# POW_CONT.net
KiCad netlist of a schematic drawn in Altium Designer
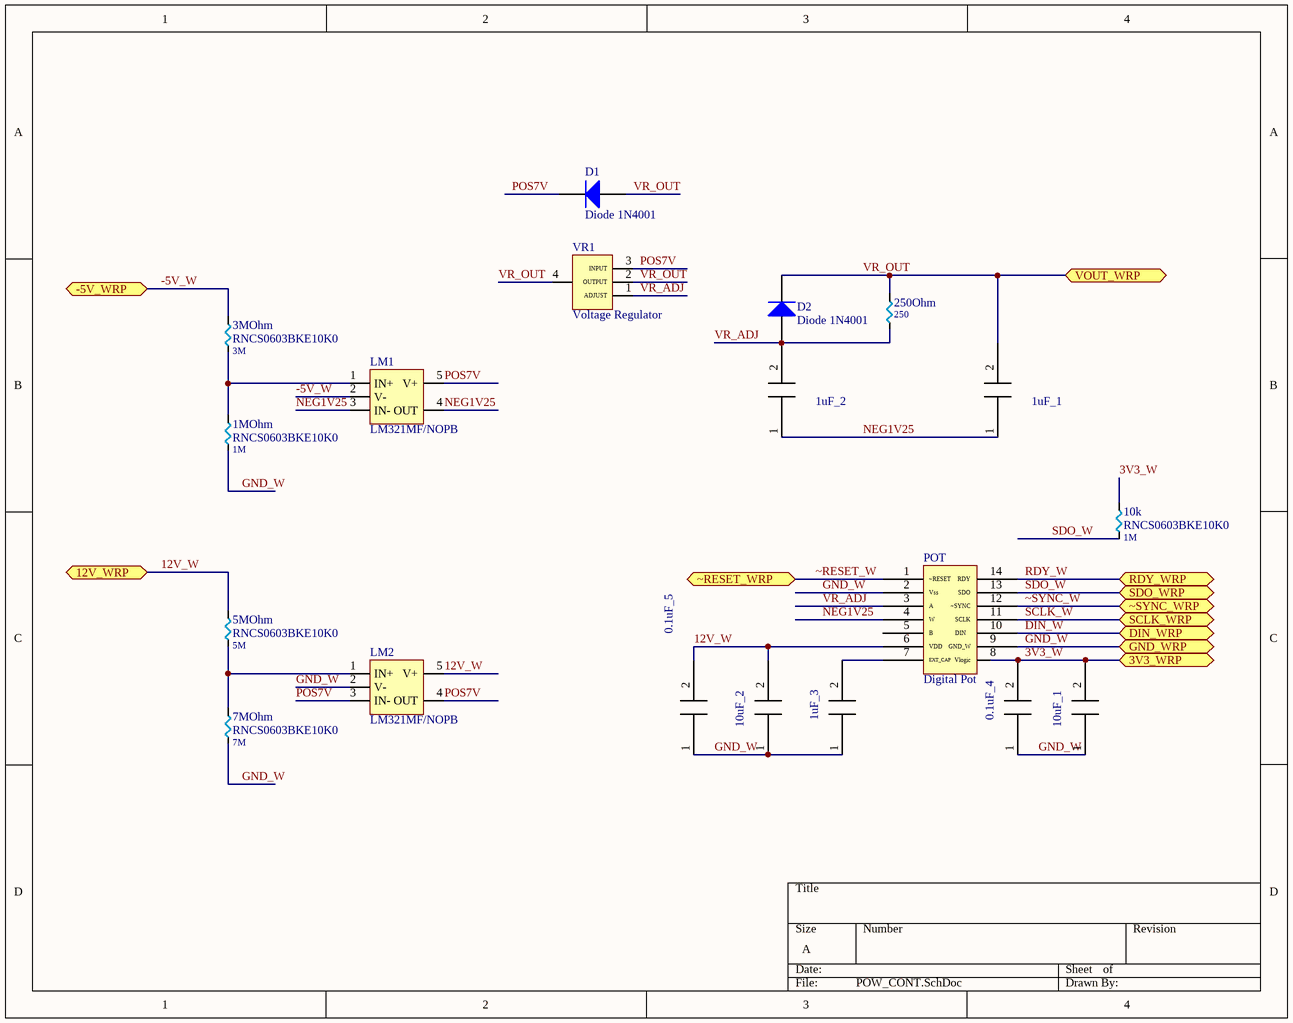
[diagram p0: POW_CONT.SchDoc]

(export (version "E")
  (design (tool "Eeschema 10.0.6"))
  (components
    (comp (ref "0.1uF_4")
      (value "0.1uF_0603")
      (footprint "0.1uF_0603")
      (libsource (lib "BBB_Board") (part "0.1uF_0603"))
    )
    (comp (ref "0.1uF_5")
      (value "0.1uF_0603")
      (footprint "0.1uF_0603")
      (libsource (lib "BBB_Board") (part "0.1uF_0603"))
    )
    (comp (ref "1MOhm")
      (value "RNCS0603BKE10K0")
      (footprint "0.1uF_0603")
      (description "RES 10K OHM 1/16W 0.1% 0603")
      (fields
        (field (name "MANUFACTURER") "Stackpole Electronics Inc")
        (field (name "TOLERANCE") "±0.1%")
        (field (name "RESISTANCE (OHMS)") "1M")
      )
      (libsource (lib "BBB_Board") (part "RNCS0603BKE10K0"))
    )
    (comp (ref "1uF_1")
      (value "0.1uF_0603")
      (footprint "0.1uF_0603")
      (libsource (lib "BBB_Board") (part "0.1uF_0603"))
    )
    (comp (ref "1uF_2")
      (value "0.1uF_0603")
      (footprint "0.1uF_0603")
      (libsource (lib "BBB_Board") (part "0.1uF_0603"))
    )
    (comp (ref "1uF_3")
      (value "0.1uF_0603")
      (footprint "0.1uF_0603")
      (libsource (lib "BBB_Board") (part "0.1uF_0603"))
    )
    (comp (ref "3MOhm")
      (value "RNCS0603BKE10K0")
      (footprint "0.1uF_0603")
      (description "RES 10K OHM 1/16W 0.1% 0603")
      (fields
        (field (name "MANUFACTURER") "Stackpole Electronics Inc")
        (field (name "TOLERANCE") "±0.1%")
        (field (name "RESISTANCE (OHMS)") "3M")
      )
      (libsource (lib "BBB_Board") (part "RNCS0603BKE10K0"))
    )
    (comp (ref "5MOhm")
      (value "RNCS0603BKE10K0")
      (footprint "0.1uF_0603")
      (description "RES 10K OHM 1/16W 0.1% 0603")
      (fields
        (field (name "MANUFACTURER") "Stackpole Electronics Inc")
        (field (name "TOLERANCE") "±0.1%")
        (field (name "RESISTANCE (OHMS)") "5M")
      )
      (libsource (lib "BBB_Board") (part "RNCS0603BKE10K0"))
    )
    (comp (ref "7MOhm")
      (value "RNCS0603BKE10K0")
      (footprint "0.1uF_0603")
      (description "RES 10K OHM 1/16W 0.1% 0603")
      (fields
        (field (name "MANUFACTURER") "Stackpole Electronics Inc")
        (field (name "TOLERANCE") "±0.1%")
        (field (name "RESISTANCE (OHMS)") "7M")
      )
      (libsource (lib "BBB_Board") (part "RNCS0603BKE10K0"))
    )
    (comp (ref "10k")
      (value "RNCS0603BKE10K0")
      (footprint "0.1uF_0603")
      (description "RES 10K OHM 1/16W 0.1% 0603")
      (fields
        (field (name "MANUFACTURER") "Stackpole Electronics Inc")
        (field (name "TOLERANCE") "±0.1%")
        (field (name "RESISTANCE (OHMS)") "1M")
      )
      (libsource (lib "BBB_Board") (part "RNCS0603BKE10K0"))
    )
    (comp (ref "10uF_1")
      (value "0.1uF_0603")
      (footprint "0.1uF_0603")
      (libsource (lib "BBB_Board") (part "0.1uF_0603"))
    )
    (comp (ref "10uF_2")
      (value "0.1uF_0603")
      (footprint "0.1uF_0603")
      (libsource (lib "BBB_Board") (part "0.1uF_0603"))
    )
    (comp (ref "250Ohm")
      (value "RNCS0603BKE10K0")
      (footprint "0.1uF_0603")
      (description "RES 10K OHM 1/16W 0.1% 0603")
      (fields
        (field (name "MANUFACTURER") "Stackpole Electronics Inc")
        (field (name "TOLERANCE") "±0.1%")
        (field (name "RESISTANCE (OHMS)") "250")
      )
      (libsource (lib "BBB_Board") (part "RNCS0603BKE10K0"))
    )
    (comp (ref "D1")
      (value "Diode 1N4001")
      (footprint "DO-41")
      (description "1 Amp General Purpose Rectifier")
      (fields (field (name "PUBLISHER") "Altium Limited"))
      (libsource (lib "Miscellaneous Devices") (part "Diode 1N4001"))
    )
    (comp (ref "D2")
      (value "Diode 1N4001")
      (footprint "DO-41")
      (description "1 Amp General Purpose Rectifier")
      (fields (field (name "PUBLISHER") "Altium Limited"))
      (libsource (lib "Miscellaneous Devices") (part "Diode 1N4001"))
    )
    (comp (ref "LM1")
      (value "LM321MF/NOPB")
      (footprint "op_amp")
      (description "IC OPAMP GP 1MHZ SOT23-5")
      (fields (field (name "MANUFACTURER") "Texas Instruments"))
      (libsource (lib "BBB_Board") (part "LM321MF/NOPB"))
    )
    (comp (ref "LM2")
      (value "LM321MF/NOPB")
      (footprint "op_amp")
      (description "IC OPAMP GP 1MHZ SOT23-5")
      (fields (field (name "MANUFACTURER") "Texas Instruments"))
      (libsource (lib "BBB_Board") (part "LM321MF/NOPB"))
    )
    (comp (ref "POT")
      (value "Digital Pot")
      (footprint "Dig_Pot")
      (description "IC DGTL POT 1024POS 20K 14TSSOP")
      (fields
        (field (name "MANUFACTURER") "Analog Devices Inc.")
        (field (name "MANUFACTURER PART NUMBER") "AD5293BRUZ-20")
      )
      (libsource (lib "BBB_Board") (part "Digital Pot"))
    )
    (comp (ref "VR1")
      (value "Voltage Regulator")
      (footprint "volt_reg")
      (description "IC REG LDO ADJ 1.5A DDPAK")
      (fields
        (field (name "MANUFACTURER") "Texas Instruments")
        (field (name "MANUFACTURER PART NUMBER") "LM317KTTR")
      )
      (libsource (lib "BBB_Board") (part "Voltage Regulator"))
    )
  )
  (nets
    (net (code "1") (name "/-5V_W") (class "Default")
      (node (ref "3MOhm") (pin "2") (pinfunction "2_2") (pintype "passive"))
      (node (ref "LM1") (pin "2") (pinfunction "V-_2") (pintype "passive"))
    )
    (net (code "2") (name "/3V3_W") (class "Default")
      (node (ref "0.1uF_4") (pin "2") (pinfunction "2_2") (pintype "passive"))
      (node (ref "10k") (pin "2") (pinfunction "2_2") (pintype "passive"))
      (node (ref "10uF_1") (pin "2") (pinfunction "2_2") (pintype "passive"))
      (node (ref "POT") (pin "8") (pinfunction "Vlogic_8") (pintype "passive"))
    )
    (net (code "3") (name "/12V_W") (class "Default")
      (node (ref "0.1uF_5") (pin "2") (pinfunction "2_2") (pintype "passive"))
      (node (ref "10uF_2") (pin "2") (pinfunction "2_2") (pintype "passive"))
      (node (ref "5MOhm") (pin "2") (pinfunction "2_2") (pintype "passive"))
      (node (ref "LM2") (pin "5") (pinfunction "V+_5") (pintype "passive"))
      (node (ref "POT") (pin "6") (pinfunction "VDD_6") (pintype "passive"))
    )
    (net (code "4") (name "/DIN_W") (class "Default")
      (node (ref "POT") (pin "10") (pinfunction "DIN_10") (pintype "passive"))
    )
    (net (code "5") (name "/GND_W") (class "Default")
      (node (ref "0.1uF_4") (pin "1") (pinfunction "1_1") (pintype "passive"))
      (node (ref "0.1uF_5") (pin "1") (pinfunction "1_1") (pintype "passive"))
      (node (ref "10uF_1") (pin "1") (pinfunction "1_1") (pintype "passive"))
      (node (ref "10uF_2") (pin "1") (pinfunction "1_1") (pintype "passive"))
      (node (ref "1MOhm") (pin "1") (pinfunction "1_1") (pintype "passive"))
      (node (ref "1uF_3") (pin "1") (pinfunction "1_1") (pintype "passive"))
      (node (ref "7MOhm") (pin "1") (pinfunction "1_1") (pintype "passive"))
      (node (ref "LM2") (pin "2") (pinfunction "V-_2") (pintype "passive"))
      (node (ref "POT") (pin "2") (pinfunction "Vss_2") (pintype "passive"))
      (node (ref "POT") (pin "9") (pinfunction "GND_W_9") (pintype "passive"))
    )
    (net (code "6") (name "/NEG1V25") (class "Default")
      (node (ref "1uF_1") (pin "1") (pinfunction "1_1") (pintype "passive"))
      (node (ref "1uF_2") (pin "1") (pinfunction "1_1") (pintype "passive"))
      (node (ref "LM1") (pin "3") (pinfunction "IN-_3") (pintype "passive"))
      (node (ref "LM1") (pin "4") (pinfunction "OUT_4") (pintype "passive"))
      (node (ref "POT") (pin "4") (pinfunction "W_4") (pintype "passive"))
    )
    (net (code "7") (name "/POS7V") (class "Default")
      (node (ref "D1") (pin "2") (pinfunction "K_2") (pintype "passive"))
      (node (ref "LM1") (pin "5") (pinfunction "V+_5") (pintype "passive"))
      (node (ref "LM2") (pin "3") (pinfunction "IN-_3") (pintype "passive"))
      (node (ref "LM2") (pin "4") (pinfunction "OUT_4") (pintype "passive"))
      (node (ref "VR1") (pin "3") (pinfunction "INPUT_3") (pintype "passive"))
    )
    (net (code "8") (name "/RDY_W") (class "Default")
      (node (ref "POT") (pin "14") (pinfunction "RDY_14") (pintype "passive"))
    )
    (net (code "9") (name "/SCLK_W") (class "Default")
      (node (ref "POT") (pin "11") (pinfunction "SCLK_11") (pintype "passive"))
    )
    (net (code "10") (name "/SDO_W") (class "Default")
      (node (ref "10k") (pin "1") (pinfunction "1_1") (pintype "passive"))
      (node (ref "POT") (pin "13") (pinfunction "SDO_13") (pintype "passive"))
    )
    (net (code "11") (name "/VR_ADJ") (class "Default")
      (node (ref "1uF_2") (pin "2") (pinfunction "2_2") (pintype "passive"))
      (node (ref "250Ohm") (pin "1") (pinfunction "1_1") (pintype "passive"))
      (node (ref "D2") (pin "1") (pinfunction "A_1") (pintype "passive"))
      (node (ref "POT") (pin "3") (pinfunction "A_3") (pintype "passive"))
      (node (ref "VR1") (pin "1") (pinfunction "ADJUST_1") (pintype "passive"))
    )
    (net (code "12") (name "/VR_OUT") (class "Default")
      (node (ref "1uF_1") (pin "2") (pinfunction "2_2") (pintype "passive"))
      (node (ref "250Ohm") (pin "2") (pinfunction "2_2") (pintype "passive"))
      (node (ref "D1") (pin "1") (pinfunction "A_1") (pintype "passive"))
      (node (ref "D2") (pin "2") (pinfunction "K_2") (pintype "passive"))
      (node (ref "VR1") (pin "2") (pinfunction "OUTPUT_2") (pintype "passive"))
      (node (ref "VR1") (pin "4") (pinfunction "Output_4") (pintype "passive"))
    )
    (net (code "13") (name "/~RESET_W") (class "Default")
      (node (ref "POT") (pin "1") (pinfunction "~RESET_1") (pintype "passive"))
    )
    (net (code "14") (name "/~SYNC_W") (class "Default")
      (node (ref "POT") (pin "12") (pinfunction "~SYNC_12") (pintype "passive"))
    )
    (net (code "15") (name "Net-(LM1-IN+)") (class "Default")
      (node (ref "1MOhm") (pin "2") (pinfunction "2_2") (pintype "passive"))
      (node (ref "3MOhm") (pin "1") (pinfunction "1_1") (pintype "passive"))
      (node (ref "LM1") (pin "1") (pinfunction "IN+_1") (pintype "passive"))
    )
    (net (code "16") (name "Net-(LM2-IN+)") (class "Default")
      (node (ref "5MOhm") (pin "1") (pinfunction "1_1") (pintype "passive"))
      (node (ref "7MOhm") (pin "2") (pinfunction "2_2") (pintype "passive"))
      (node (ref "LM2") (pin "1") (pinfunction "IN+_1") (pintype "passive"))
    )
    (net (code "17") (name "Net-(POT-EXT_CAP)") (class "Default")
      (node (ref "1uF_3") (pin "2") (pinfunction "2_2") (pintype "passive"))
      (node (ref "POT") (pin "7") (pinfunction "EXT_CAP_7") (pintype "passive"))
    )
    (net (code "18") (name "unconnected-(POT-B-Pad5)") (class "Default")
      (node (ref "POT") (pin "5") (pinfunction "B_5") (pintype "passive"))
    )
  )
)
